# 04-USB.net
KiCad netlist of a schematic drawn in Altium Designer
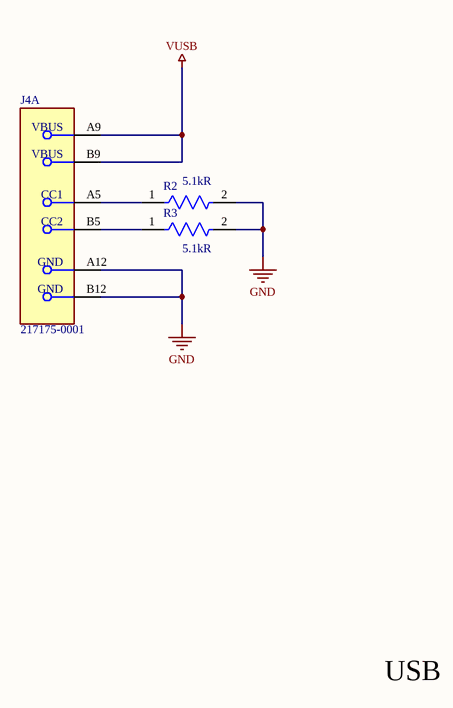
[diagram p0: 04-USB.SchDoc]

(export (version "E")
  (design (tool "Eeschema 10.0.6"))
  (components
    (comp (ref "J4")
      (value "217175-0001")
      (footprint "FP-217175-0001-MFG")
      (description "CONN RCP USB2.0 C 6+18P SMD RA")
      (libsource (lib "Altium Content Vault") (part "6a66c69350f09309f94811689c98437"))
    )
    (comp (ref "R2")
      (value "5.1kR")
      (footprint "FP-RN73R2A-IPC_C")
      (description "5.1kΩ ±0.05% 0.125W, 1/8W Chip Resistor 0805 (2012 Metric) Moisture Resistant Thin Film")
      (libsource (lib "Altium Content Vault") (part "1029c3af85768c4190bb7ad29bc67b5"))
    )
    (comp (ref "R3")
      (value "5.1kR")
      (footprint "FP-RN73R2A-IPC_C")
      (description "5.1kΩ ±0.05% 0.125W, 1/8W Chip Resistor 0805 (2012 Metric) Moisture Resistant Thin Film")
      (libsource (lib "Altium Content Vault") (part "1029c3af85768c4190bb7ad29bc67b5"))
    )
  )
  (nets
    (net (code "1") (name "GND") (class "Default")
      (node (ref "J4") (pin "A12") (pinfunction "GND_A12") (pintype "power_in"))
      (node (ref "J4") (pin "B12") (pinfunction "GND_B12") (pintype "power_in"))
      (node (ref "R2") (pin "2") (pinfunction "2_2") (pintype "passive"))
      (node (ref "R3") (pin "2") (pinfunction "2_2") (pintype "passive"))
    )
    (net (code "2") (name "Net-(J4A-CC1)") (class "Default")
      (node (ref "J4") (pin "A5") (pinfunction "CC1_A5") (pintype "passive"))
      (node (ref "R2") (pin "1") (pinfunction "1_1") (pintype "passive"))
    )
    (net (code "3") (name "Net-(J4A-CC2)") (class "Default")
      (node (ref "J4") (pin "B5") (pinfunction "CC2_B5") (pintype "passive"))
      (node (ref "R3") (pin "1") (pinfunction "1_1") (pintype "passive"))
    )
    (net (code "4") (name "VUSB") (class "Default")
      (node (ref "J4") (pin "A9") (pinfunction "VBUS_A9") (pintype "power_in"))
      (node (ref "J4") (pin "B9") (pinfunction "VBUS_B9") (pintype "power_in"))
    )
  )
)
